# Coffee_printer_PWR.net
KiCad netlist of a schematic drawn in Altium Designer
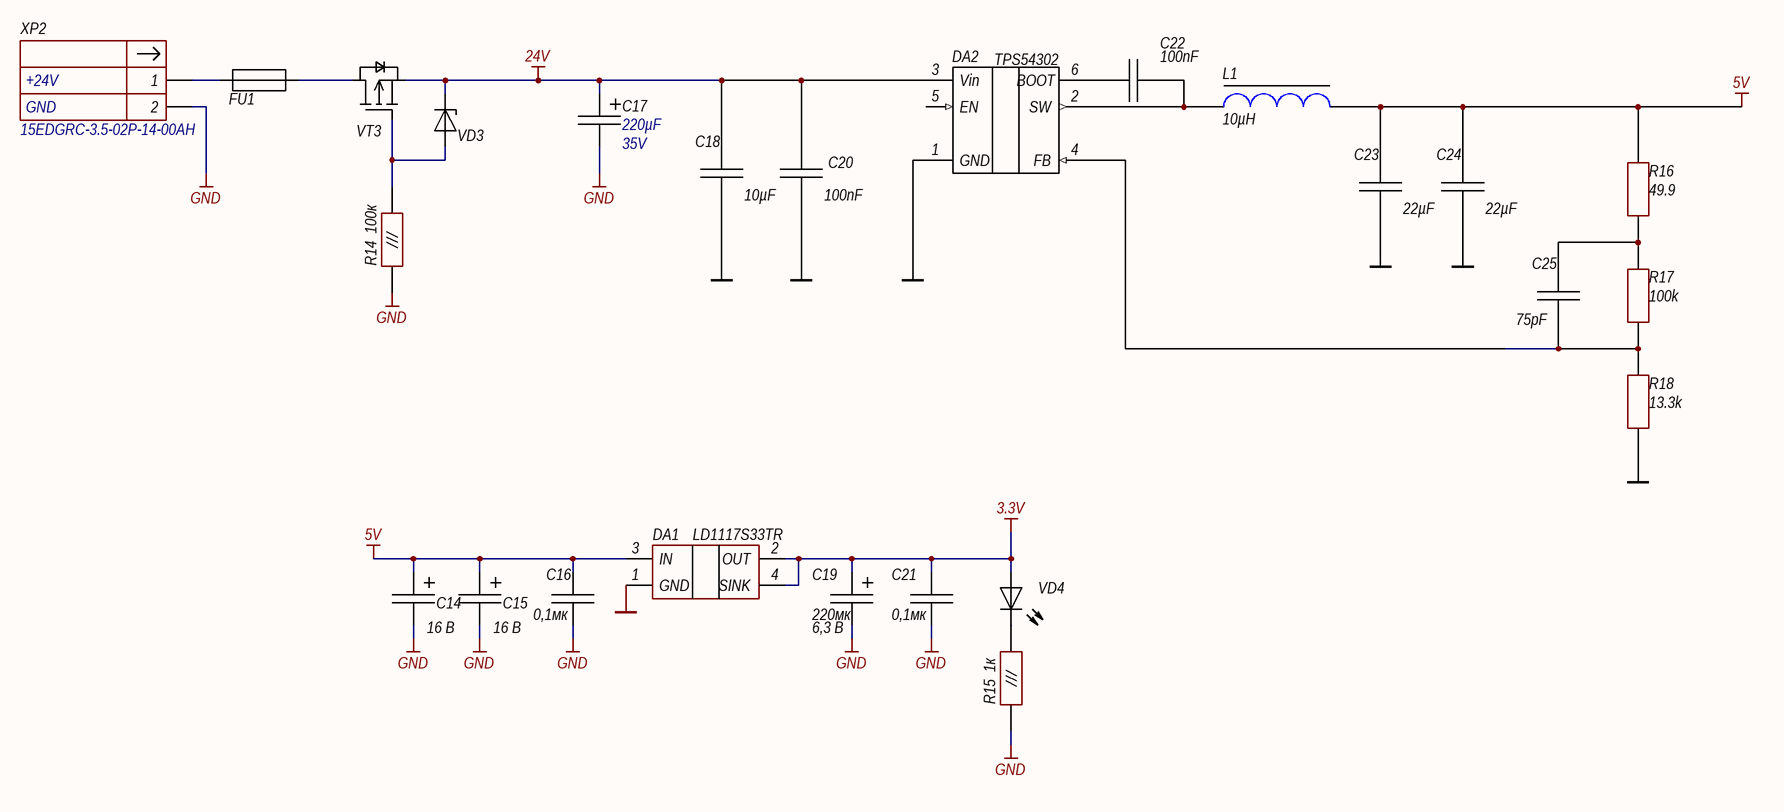
[diagram p0: Coffee_printer PWR.SchDoc]

(export (version "E")
  (design (tool "Eeschema 10.0.6"))
  (components
    (comp (ref "C14")
      (value "100мк")
      (footprint "CAPELSMD_D6.3_H5.5")
      (description "CAP ALUM 100UF 20% 16V SMD")
      (fields
        (field (name "VOLTAGE") "16 В")
        (field (name "PARTNUMBER") "CA016M0100RED-0605_Yageo")
        (field (name "MANUFACTURER") "Yageo")
        (field (name "АВТОР") "Жегалов Сергей")
      )
      (libsource (lib "EncataLIB") (part "C_POLAR"))
    )
    (comp (ref "C15")
      (value "100мк")
      (footprint "CAPELSMD_D6.3_H5.5")
      (description "CAP ALUM 100UF 20% 16V SMD")
      (fields
        (field (name "VOLTAGE") "16 В")
        (field (name "PARTNUMBER") "CA016M0100RED-0605_Yageo")
        (field (name "MANUFACTURER") "Yageo")
        (field (name "АВТОР") "Жегалов Сергей")
      )
      (libsource (lib "EncataLIB") (part "C_POLAR"))
    )
    (comp (ref "C16")
      (value "0,1мк")
      (footprint "CAPC0805_H1.0_N")
      (description "CAPC 0.1uF 50V X7R SMD 0805")
      (fields
        (field (name "PARTNUMBER") "CC0805KPX7R9BB104_Yageo")
        (field (name "MANUFACTURER") "Yageo")
        (field (name "MODIFY") "Чт, 15.11.2018 9:22:46")
        (field (name "АВТОР") "Жегалов Сергей")
      )
      (libsource (lib "EncataLIB") (part "C"))
    )
    (comp (ref "C17")
      (value "EEEFK1V221P")
      (footprint "CAPELSMD_D8_H10.2")
      (description "35V 220uF 105°C (8x10,2mm )2000Hours")
      (fields
        (field (name "CAPACITANCE") "220µF")
        (field (name "MANUFACTURER") "Panasonic")
        (field (name "TOLERANCE") "20%")
        (field (name "VOLTAGE RATING") "35V")
        (field (name "AUTHOR") "M.S.Koval")
      )
      (libsource (lib "EnCata Concord Pro") (part "С_POLAR"))
    )
    (comp (ref "C18")
      (value "CL32B106KBJNFNE")
      (footprint "CAPC1210_H2.2_N")
      (description "10uF 10% X7R 50V 1210")
      (fields
        (field (name "CAPACITANCE") "10µF")
        (field (name "MANUFACTURER") "Samsung")
        (field (name "TOLERANCE") "10%")
        (field (name "AUTHOR") "V.Kisel")
      )
      (libsource (lib "EnCata Concord Pro") (part "C"))
    )
    (comp (ref "C19")
      (value "220мк")
      (footprint "CAPTAN_C_N")
      (description "CAPTAN 220uF 10% 6.3V SMD_6032-28(size_C)")
      (fields
        (field (name "VOLTAGE") "6,3 В")
        (field (name "PARTNUMBER") "293D227X96R3C2TE3_Vishay Semiconductor")
        (field (name "MANUFACTURER") "Vishay Semiconductor")
        (field (name "MODIFY") "Ср, 21.11.2018 9:22:46")
        (field (name "АВТОР") "Жегалов Сергей")
      )
      (libsource (lib "EncataLIB") (part "C_POLAR"))
    )
    (comp (ref "C20")
      (value "CC0603KRX7R7BB104")
      (footprint "CAPC0603_H0.90_N")
      (description "0.1uF 10% X7R 16V 0603")
      (fields
        (field (name "TOLERANCE") "10%")
        (field (name "CAPACITANCE") "100nF")
        (field (name "MANUFACTURER") "Yageo")
        (field (name "AUTHOR") "v.ivanchenko")
      )
      (libsource (lib "EnCata Concord Pro") (part "C"))
    )
    (comp (ref "C21")
      (value "0,1мк")
      (footprint "CAPC0805_H1.0_N")
      (description "CAPC 0.1uF 50V X7R SMD 0805")
      (fields
        (field (name "PARTNUMBER") "CC0805KPX7R9BB104_Yageo")
        (field (name "MANUFACTURER") "Yageo")
        (field (name "MODIFY") "Чт, 15.11.2018 9:22:46")
        (field (name "АВТОР") "Жегалов Сергей")
      )
      (libsource (lib "EncataLIB") (part "C"))
    )
    (comp (ref "C22")
      (value "CC0603KRX7R7BB104")
      (footprint "CAPC0603_H0.90_N")
      (description "0.1uF 10% X7R 16V 0603")
      (fields
        (field (name "TOLERANCE") "10%")
        (field (name "CAPACITANCE") "100nF")
        (field (name "MANUFACTURER") "Yageo")
        (field (name "AUTHOR") "v.ivanchenko")
      )
      (libsource (lib "EnCata Concord Pro") (part "C"))
    )
    (comp (ref "C23")
      (value "CL32B226KAJNNNE")
      (footprint "CAPC1210_H2.2_N")
      (description "Ceramic capacitor SMD-1210 22000nF (22uF) /25V X7R# K +- 10% Samsung, RoHS/4k/")
      (fields
        (field (name "CAPACITANCE") "22µF")
        (field (name "MANUFACTURER") "Samsung")
        (field (name "TOLERANCE") "10%")
        (field (name "AUTHOR") "V.Kisel")
      )
      (libsource (lib "EnCata Concord Pro") (part "C"))
    )
    (comp (ref "C24")
      (value "CL32B226KAJNNNE")
      (footprint "CAPC1210_H2.2_N")
      (description "Ceramic capacitor SMD-1210 22000nF (22uF) /25V X7R# K +- 10% Samsung, RoHS/4k/")
      (fields
        (field (name "CAPACITANCE") "22µF")
        (field (name "MANUFACTURER") "Samsung")
        (field (name "TOLERANCE") "10%")
        (field (name "AUTHOR") "V.Kisel")
      )
      (libsource (lib "EnCata Concord Pro") (part "C"))
    )
    (comp (ref "C25")
      (value "CC0603JRNPO9BN750")
      (footprint "CAPC0603_H0.90_N")
      (description "0603 75 pF 50 V ±5 % Tolerance NP0 SMT Multilayer Ceramic Capacitor")
      (fields
        (field (name "TOLERANCE") "5%")
        (field (name "CAPACITANCE") "75pF")
        (field (name "MANUFACTURER") "Yageo")
        (field (name "AUTHOR") "V.Kisel")
      )
      (libsource (lib "EnCata Concord Pro") (part "C"))
    )
    (comp (ref "DA1")
      (value "LD1117S33TR")
      (footprint "SOT-223")
      (description "DA LD1117S33TR REG LINEAR 3.3V 800MA SOT223")
      (fields
        (field (name "PARTNUMBER") "LD1117S33TR_STMicroelectronics")
        (field (name "MANUFACTURER") "STMicroelectronics")
        (field (name "MODIFY") "Пн, 26.11.2018 11:39:06")
        (field (name "АВТОР") "Дёмин Виктор")
      )
      (libsource (lib "EncataLIB") (part "DA_LD1117"))
    )
    (comp (ref "DA2")
      (value "TPS54302")
      (footprint "SOT-23-6")
      (description "4.5-V to 28-V Input, 3-A Output, EMI Friendly Synchronous Step-Down Converter")
      (fields (field (name "MANUFACTURER") "Texas Instruments") (field (name "AUTHOR") "V.Kisel"))
      (libsource (lib "EnCata Concord Pro") (part "TPS54302"))
    )
    (comp (ref "FU1")
      (value "0451001.MRL")
      (footprint "SMT_FUSE_451_453")
      (description "FU_0451001.MRL 1A 125V FUSE SMT")
      (fields
        (field (name "PARTNUMBER") "0451001.MRL_Littelfuse")
        (field (name "MANUFACTURER") "Littelfuse")
        (field (name "АВТОР") "Касперович Андрей")
      )
      (libsource (lib "EncataLIB") (part "FU_0451001.MRL"))
    )
    (comp (ref "L1")
      (value "IHLP2525CZER100M11")
      (footprint "IHLP2525")
      (description "SMD2525 10uH 4A/3.5A 50V 71.2 mOhm")
      (fields
        (field (name "INDUCTANCE") "10µH")
        (field (name "MANUFACTURER") "Vishay")
        (field (name "TOLERANCE") "20%")
        (field (name "AUTHOR") "V.Kisel")
      )
      (libsource (lib "EnCata Concord Pro") (part "L_CORE"))
    )
    (comp (ref "R14")
      (value "100к")
      (footprint "RESC0603_N")
      (description "RES 100K SMD 0603 1%")
      (fields
        (field (name "PARTNUMBER") "RC0603FR-07100KL_Yageo")
        (field (name "MANUFACTURERPARTNUMBER") "RC0603FR-07100KL")
        (field (name "АВТОР") "Анципов Антон")
      )
      (libsource (lib "EncataLIB") (part "R_0.05W"))
    )
    (comp (ref "R15")
      (value "1к")
      (footprint "RESC0603_N")
      (description "RES 1k SMD 0603 1%")
      (fields
        (field (name "PARTNUMBER") "RC0603FR-071KL_Yageo")
        (field (name "MANUFACTURER") "Yageo")
        (field (name "АВТОР") "Анципов Антон")
      )
      (libsource (lib "EncataLIB") (part "R_0.05W"))
    )
    (comp (ref "R16")
      (value "RC0603FR-0749R9L")
      (footprint "RESC0603_N")
      (description "Res General Purpose Thick Film 0603 49.9 Ohm 1% 1/10W ±100ppm/°C Molded SMD Paper T/R")
      (fields
        (field (name "MANUFACTURER") "Yageo")
        (field (name "RESISTANCE") "49.9")
        (field (name "TOLERANCE") "1%")
        (field (name "AUTHOR") "V.Kisel")
      )
      (libsource (lib "EnCata Concord Pro") (part "R_GENERAL"))
    )
    (comp (ref "R17")
      (value "RC0603FR-07100KL")
      (footprint "RESC0603_N")
      (description "RES SMD 100 KOHM 1% 1/10W 0603")
      (fields
        (field (name "MANUFACTURER") "Yageo")
        (field (name "RESISTANCE") "100k")
        (field (name "TOLERANCE") "1%")
        (field (name "AUTHOR") "M.S. Koval")
      )
      (libsource (lib "EnCata Concord Pro") (part "R_GENERAL"))
    )
    (comp (ref "R18")
      (value "RC0603FR-0713K3L")
      (footprint "RESC0603_N")
      (description "RES SMD 13.3K OHM 1% 1/10W 0603")
      (fields
        (field (name "MANUFACTURER") "Yageo")
        (field (name "RESISTANCE") "13.3k")
        (field (name "TOLERANCE") "1%")
        (field (name "AUTHOR") "M.S. Koval")
      )
      (libsource (lib "EnCata Concord Pro") (part "R_GENERAL"))
    )
    (comp (ref "VD3")
      (value "MMSZ12T1G")
      (footprint "SOD-123")
      (description "Zener diode 500mW 12V  ±5% SOD-123")
      (fields
        (field (name "PARTNUMBER") "MMSZ12T1G_ON Semiconductor")
        (field (name "MANUFACTURER") "ON Semiconductor")
        (field (name "АВТОР") "Касперович Андрей")
      )
      (libsource (lib "EncataLIB") (part "VD_ZENER"))
    )
    (comp (ref "VD4")
      (value "FYLS-0603UGC")
      (footprint "CH0603LG")
      (description "VD FYLS-0603UGC LED GREEN 20mA 2V SMD 0603")
      (fields
        (field (name "PARTNUMBER") "FYLS-0603UGC_Foryard Optoelectronics")
        (field (name "MANUFACTURER") "Foryard Optoelectronics")
        (field (name "MODIFY") "Пн, 14.01.2019 13:57:40")
        (field (name "АВТОР") "Коваль Максим")
      )
      (libsource (lib "EncataLIB") (part "VD_LED"))
    )
    (comp (ref "VT3")
      (value "SI7617DN-T1-GE3")
      (footprint "PowerPAK 1212-8")
      (description "MOSFET P-CH 30V 35A 1212-8 PPAK")
      (fields
        (field (name "MANUFACTURER PART NUMBER") "Si7615ADN")
        (field (name "MANUFACTURER") "Vishay")
        (field (name "AUTHOR") "m.seliadtsou")
      )
      (libsource (lib "EnCata Concord Pro") (part "MOSFET P-ch (1G-2S-3D)"))
    )
    (comp (ref "XP2")
      (value "15EDGRC-3.5-02P-14-00AH")
      (footprint "15EDGRC-3.5-02P-14-00AH")
      (description "2 pin, 3.5mm, 8A, 250V")
      (fields
        (field (name "NET1") "+24V")
        (field (name "NET2") "GND")
        (field (name "MANUFACTURER") "Degson")
        (field (name "AUTHOR") "a.antipov")
      )
      (libsource (lib "EnCata Concord Pro") (part "XP2"))
    )
  )
  (nets
    (net (code "1") (name "3.3V") (class "Default")
      (node (ref "C19") (pin "1") (pinfunction "1_1") (pintype "passive"))
      (node (ref "C21") (pin "1") (pinfunction "1_1") (pintype "passive"))
      (node (ref "DA1") (pin "2") (pinfunction "OUT_2") (pintype "power_in"))
      (node (ref "DA1") (pin "4") (pinfunction "SINK_4") (pintype "power_in"))
      (node (ref "VD4") (pin "1") (pinfunction "1_1") (pintype "passive"))
    )
    (net (code "2") (name "5V") (class "Default")
      (node (ref "C14") (pin "1") (pinfunction "1_1") (pintype "passive"))
      (node (ref "C15") (pin "1") (pinfunction "1_1") (pintype "passive"))
      (node (ref "C16") (pin "1") (pinfunction "1_1") (pintype "passive"))
      (node (ref "C23") (pin "1") (pinfunction "1_1") (pintype "passive"))
      (node (ref "C24") (pin "1") (pinfunction "1_1") (pintype "passive"))
      (node (ref "DA1") (pin "3") (pinfunction "IN_3") (pintype "power_in"))
      (node (ref "L1") (pin "2") (pinfunction "2_2") (pintype "passive"))
      (node (ref "R16") (pin "2") (pinfunction "2_2") (pintype "passive"))
    )
    (net (code "4") (name "24V") (class "Default")
      (node (ref "C17") (pin "1") (pinfunction "1_1") (pintype "passive"))
      (node (ref "C18") (pin "1") (pinfunction "1_1") (pintype "passive"))
      (node (ref "C20") (pin "2") (pinfunction "2_2") (pintype "passive"))
      (node (ref "DA2") (pin "3") (pinfunction "Vin_3") (pintype "power_in"))
      (node (ref "VD3") (pin "2") (pinfunction "2_2") (pintype "passive"))
      (node (ref "VT3") (pin "2") (pinfunction "S_2") (pintype "passive"))
    )
    (net (code "5") (name "GND") (class "Default")
      (node (ref "C14") (pin "2") (pinfunction "2_2") (pintype "passive"))
      (node (ref "C15") (pin "2") (pinfunction "2_2") (pintype "passive"))
      (node (ref "C16") (pin "2") (pinfunction "2_2") (pintype "passive"))
      (node (ref "C17") (pin "2") (pinfunction "2_2") (pintype "passive"))
      (node (ref "C18") (pin "2") (pinfunction "2_2") (pintype "passive"))
      (node (ref "C19") (pin "2") (pinfunction "2_2") (pintype "passive"))
      (node (ref "C20") (pin "1") (pinfunction "1_1") (pintype "passive"))
      (node (ref "C21") (pin "2") (pinfunction "2_2") (pintype "passive"))
      (node (ref "C23") (pin "2") (pinfunction "2_2") (pintype "passive"))
      (node (ref "C24") (pin "2") (pinfunction "2_2") (pintype "passive"))
      (node (ref "DA1") (pin "1") (pinfunction "GND_1") (pintype "power_in"))
      (node (ref "DA2") (pin "1") (pinfunction "GND_1") (pintype "power_in"))
      (node (ref "R14") (pin "1") (pinfunction "1_1") (pintype "passive"))
      (node (ref "R15") (pin "1") (pinfunction "1_1") (pintype "passive"))
      (node (ref "R18") (pin "1") (pinfunction "1_1") (pintype "passive"))
      (node (ref "XP2") (pin "2") (pinfunction "2_2") (pintype "passive"))
    )
    (net (code "6") (name "Net-(C25-Pad1)") (class "Default")
      (node (ref "C25") (pin "1") (pinfunction "1_1") (pintype "passive"))
      (node (ref "R16") (pin "1") (pinfunction "1_1") (pintype "passive"))
      (node (ref "R17") (pin "2") (pinfunction "2_2") (pintype "passive"))
    )
    (net (code "7") (name "Net-(DA2-BOOT)") (class "Default")
      (node (ref "C22") (pin "1") (pinfunction "1_1") (pintype "passive"))
      (node (ref "DA2") (pin "6") (pinfunction "BOOT_6") (pintype "power_in"))
    )
    (net (code "8") (name "Net-(DA2-FB)") (class "Default")
      (node (ref "C25") (pin "2") (pinfunction "2_2") (pintype "passive"))
      (node (ref "DA2") (pin "4") (pinfunction "FB_4") (pintype "input"))
      (node (ref "R17") (pin "1") (pinfunction "1_1") (pintype "passive"))
      (node (ref "R18") (pin "2") (pinfunction "2_2") (pintype "passive"))
    )
    (net (code "9") (name "Net-(DA2-SW)") (class "Default")
      (node (ref "C22") (pin "2") (pinfunction "2_2") (pintype "passive"))
      (node (ref "DA2") (pin "2") (pinfunction "SW_2") (pintype "output"))
      (node (ref "L1") (pin "1") (pinfunction "1_1") (pintype "passive"))
    )
    (net (code "10") (name "Net-(FU1-Pad1)") (class "Default")
      (node (ref "FU1") (pin "1") (pinfunction "1_1") (pintype "passive"))
      (node (ref "XP2") (pin "1") (pinfunction "1_1") (pintype "passive"))
    )
    (net (code "11") (name "Net-(R15-Pad2)") (class "Default")
      (node (ref "R15") (pin "2") (pinfunction "2_2") (pintype "passive"))
      (node (ref "VD4") (pin "2") (pinfunction "2_2") (pintype "passive"))
    )
    (net (code "12") (name "Net-(VT3-D)") (class "Default")
      (node (ref "FU1") (pin "2") (pinfunction "2_2") (pintype "passive"))
      (node (ref "VT3") (pin "3") (pinfunction "D_3") (pintype "passive"))
    )
    (net (code "13") (name "Net-(VT3-G)") (class "Default")
      (node (ref "R14") (pin "2") (pinfunction "2_2") (pintype "passive"))
      (node (ref "VD3") (pin "1") (pinfunction "1_1") (pintype "passive"))
      (node (ref "VT3") (pin "1") (pinfunction "G_1") (pintype "passive"))
    )
    (net (code "14") (name "unconnected-(DA2-EN-Pad5)") (class "Default")
      (node (ref "DA2") (pin "5") (pinfunction "EN_5") (pintype "input"))
    )
  )
)
